# TamaDroppy.net
KiCad netlist of a schematic drawn in EAGLE
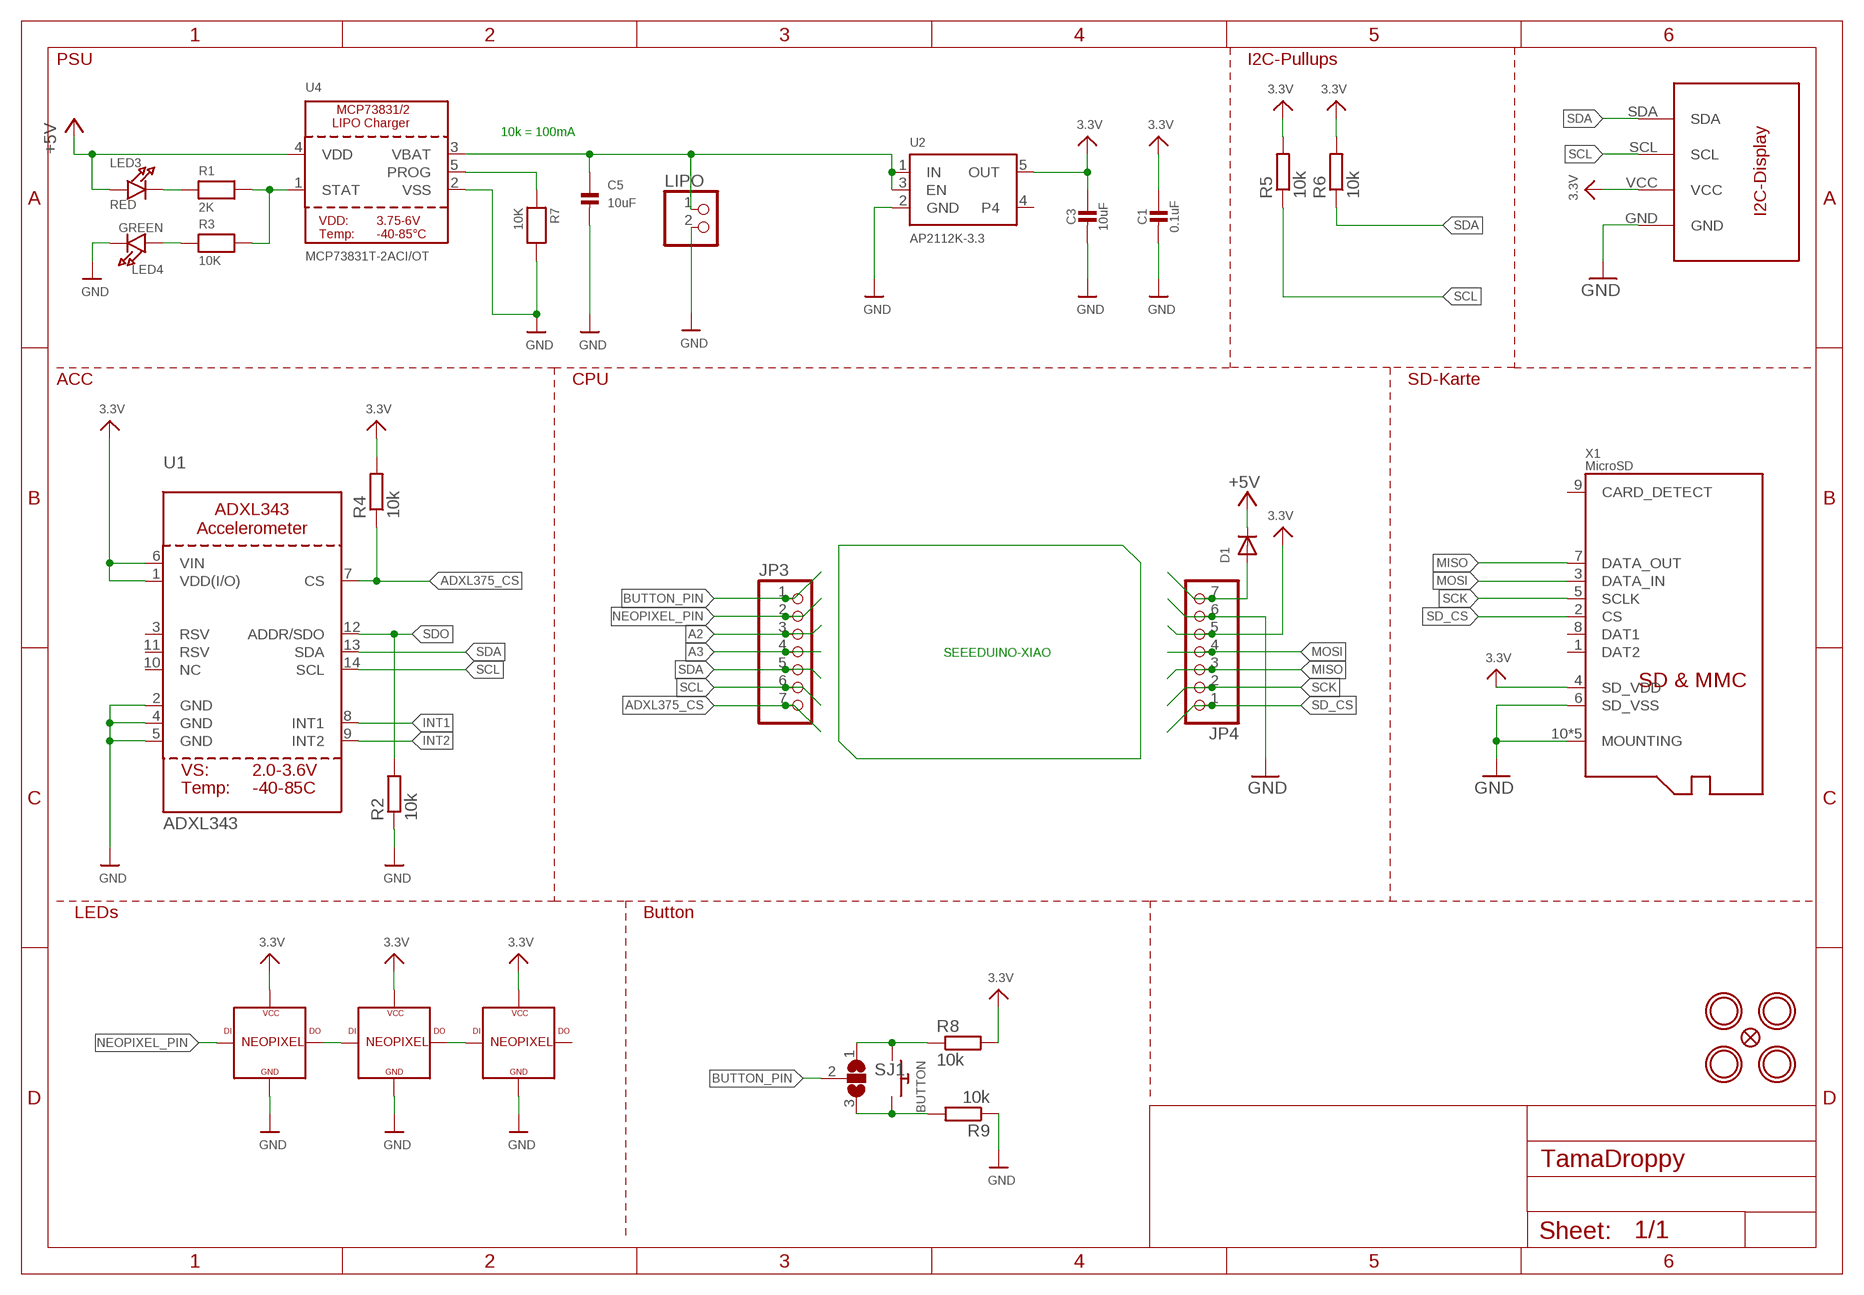
[diagram p0: schematic, sheet 1]

(export (version "E")
  (design (tool "Eeschema 10.0.6"))
  (components
    (comp (ref "BUTTON")
      (value "SWITCH_PUSHBUTTONC&K_KSS")
      (footprint "eagle-import:BTN_CK_KSS")
      (libsource (lib "eagle-import") (part "SWITCH_PUSHBUTTONC&K_KSS"))
    )
    (comp (ref "C1")
      (value "0.1uF")
      (footprint "eagle-import:0603-NO")
      (libsource (lib "eagle-import") (part "CAP_CERAMIC0603_NO"))
    )
    (comp (ref "C3")
      (value "10uF")
      (footprint "eagle-import:0805-NO")
      (libsource (lib "eagle-import") (part "CAP_CERAMIC0805-NOOUTLINE"))
    )
    (comp (ref "C5")
      (value "10uF")
      (footprint "eagle-import:0805-NO")
      (libsource (lib "eagle-import") (part "CAP_CERAMIC0805-NOOUTLINE"))
    )
    (comp (ref "D1")
      (value "DIODESOD-323F")
      (footprint "eagle-import:SOD-323F")
      (libsource (lib "eagle-import") (part "DIODESOD-323F"))
    )
    (comp (ref "FID3")
      (value "FIDUCIAL_1MM")
      (footprint "eagle-import:FIDUCIAL_1MM")
      (libsource (lib "eagle-import") (part "FIDUCIAL_1MM"))
    )
    (comp (ref "JP3")
      (value "HEADER-1X7THICKER")
      (footprint "eagle-import:1X07_ROUND_76")
      (libsource (lib "eagle-import") (part "HEADER-1X7THICKER"))
    )
    (comp (ref "JP4")
      (value "HEADER-1X7THICKER")
      (footprint "eagle-import:1X07_ROUND_76")
      (libsource (lib "eagle-import") (part "HEADER-1X7THICKER"))
    )
    (comp (ref "LED3")
      (value "RED")
      (footprint "eagle-import:CHIPLED_0603_NOOUTLINE")
      (libsource (lib "eagle-import") (part "LED0603_NOOUTLINE"))
    )
    (comp (ref "LED4")
      (value "GREEN")
      (footprint "eagle-import:CHIPLED_0603_NOOUTLINE")
      (libsource (lib "eagle-import") (part "LED0603_NOOUTLINE"))
    )
    (comp (ref "LIPO")
      (value "PINHD-1X2")
      (footprint "eagle-import:1X02")
      (libsource (lib "eagle-import") (part "PINHD-1X2"))
    )
    (comp (ref "R1")
      (value "2K")
      (footprint "eagle-import:0603-NO")
      (libsource (lib "eagle-import") (part "RESISTOR_0603_NOOUT"))
    )
    (comp (ref "R2")
      (value "10k")
      (footprint "eagle-import:M0805")
      (libsource (lib "eagle-import") (part "R-EU_M0805"))
    )
    (comp (ref "R3")
      (value "10K")
      (footprint "eagle-import:0603-NO")
      (libsource (lib "eagle-import") (part "RESISTOR_0603_NOOUT"))
    )
    (comp (ref "R4")
      (value "10k")
      (footprint "eagle-import:M0805")
      (libsource (lib "eagle-import") (part "R-EU_M0805"))
    )
    (comp (ref "R5")
      (value "10k")
      (footprint "eagle-import:M0805")
      (libsource (lib "eagle-import") (part "R-EU_M0805"))
    )
    (comp (ref "R6")
      (value "10k")
      (footprint "eagle-import:M0805")
      (libsource (lib "eagle-import") (part "R-EU_M0805"))
    )
    (comp (ref "R7")
      (value "10K")
      (footprint "eagle-import:0603-NO")
      (libsource (lib "eagle-import") (part "RESISTOR_0603_NOOUT"))
    )
    (comp (ref "R8")
      (value "10k")
      (footprint "eagle-import:M0805")
      (libsource (lib "eagle-import") (part "R-EU_M0805"))
    )
    (comp (ref "R9")
      (value "10k")
      (footprint "eagle-import:M0805")
      (libsource (lib "eagle-import") (part "R-EU_M0805"))
    )
    (comp (ref "SJ1")
      (value "SJ2W")
      (footprint "eagle-import:SJ_2")
      (libsource (lib "eagle-import") (part "SJ2W"))
    )
    (comp (ref "U$2")
      (value "MOUNTINGHOLE2.5")
      (footprint "eagle-import:MOUNTINGHOLE_2.5_PLATED")
      (libsource (lib "eagle-import") (part "MOUNTINGHOLE2.5"))
    )
    (comp (ref "U$16")
      (value "EASTRISING_0.66")
      (footprint "eagle-import:EASTRISING_0.66")
      (libsource (lib "eagle-import") (part "EASTRISING_0.66"))
    )
    (comp (ref "U$17")
      (value "MOUNTINGHOLE2.5")
      (footprint "eagle-import:MOUNTINGHOLE_2.5_PLATED")
      (libsource (lib "eagle-import") (part "MOUNTINGHOLE2.5"))
    )
    (comp (ref "U$19")
      (value "MOUNTINGHOLE2.5")
      (footprint "eagle-import:MOUNTINGHOLE_2.5_PLATED")
      (libsource (lib "eagle-import") (part "MOUNTINGHOLE2.5"))
    )
    (comp (ref "U$21")
      (value "MOUNTINGHOLE2.5")
      (footprint "eagle-import:MOUNTINGHOLE_2.5_PLATED")
      (libsource (lib "eagle-import") (part "MOUNTINGHOLE2.5"))
    )
    (comp (ref "U$31")
      (value "WS2812_BOB")
      (footprint "eagle-import:WS2812B")
      (libsource (lib "eagle-import") (part "WS2812_BOB"))
    )
    (comp (ref "U$32")
      (value "WS2812_BOB")
      (footprint "eagle-import:WS2812B")
      (libsource (lib "eagle-import") (part "WS2812_BOB"))
    )
    (comp (ref "U$33")
      (value "WS2812_BOB")
      (footprint "eagle-import:WS2812B")
      (libsource (lib "eagle-import") (part "WS2812_BOB"))
    )
    (comp (ref "U1")
      (value "ADXL343")
      (footprint "eagle-import:LGA14")
      (libsource (lib "eagle-import") (part "ACCEL_ADXL343"))
    )
    (comp (ref "U2")
      (value "AP2112K-3.3")
      (footprint "eagle-import:SOT23-5")
      (libsource (lib "eagle-import") (part "VREG_SOT23-5"))
    )
    (comp (ref "U4")
      (value "MCP73831T-2ACI/OT")
      (footprint "eagle-import:SOT23-5")
      (libsource (lib "eagle-import") (part "MCP73831/2"))
    )
    (comp (ref "X1")
      (value "MicroSD")
      (footprint "eagle-import:MOLEX_104031-0811")
      (libsource (lib "eagle-import") (part "MICROSD104031-0811"))
    )
  )
  (nets
    (net (code "1") (name "+5V") (class "Default")
      (node (ref "D1") (pin "C") (pinfunction "C_C") (pintype "passive"))
      (node (ref "LED3") (pin "A") (pinfunction "A_A") (pintype "passive"))
      (node (ref "U4") (pin "4") (pinfunction "VDD_4") (pintype "power_in"))
    )
    (net (code "2") (name "3.3V") (class "Default")
      (node (ref "C1") (pin "1") (pinfunction "1_1") (pintype "passive"))
      (node (ref "C3") (pin "1") (pinfunction "1_1") (pintype "passive"))
      (node (ref "JP4") (pin "5") (pinfunction "5_5") (pintype "passive"))
      (node (ref "R4") (pin "2") (pinfunction "2_2") (pintype "passive"))
      (node (ref "R5") (pin "2") (pinfunction "2_2") (pintype "passive"))
      (node (ref "R6") (pin "2") (pinfunction "2_2") (pintype "passive"))
      (node (ref "R8") (pin "2") (pinfunction "2_2") (pintype "passive"))
      (node (ref "U$16") (pin "VCC") (pinfunction "VCC_VCC") (pintype "bidirectional"))
      (node (ref "U$31") (pin "VCC1") (pinfunction "VCC_VCC1") (pintype "bidirectional"))
      (node (ref "U$31") (pin "VCC2") (pinfunction "VCC_VCC2") (pintype "bidirectional"))
      (node (ref "U$32") (pin "VCC1") (pinfunction "VCC_VCC1") (pintype "bidirectional"))
      (node (ref "U$32") (pin "VCC2") (pinfunction "VCC_VCC2") (pintype "bidirectional"))
      (node (ref "U$33") (pin "VCC1") (pinfunction "VCC_VCC1") (pintype "bidirectional"))
      (node (ref "U$33") (pin "VCC2") (pinfunction "VCC_VCC2") (pintype "bidirectional"))
      (node (ref "U1") (pin "1") (pinfunction "VDD(I/O)_1") (pintype "bidirectional"))
      (node (ref "U1") (pin "6") (pinfunction "VIN_6") (pintype "bidirectional"))
      (node (ref "U2") (pin "5") (pinfunction "OUT_5") (pintype "power_in"))
      (node (ref "X1") (pin "4") (pinfunction "SD_VDD_4") (pintype "power_in"))
    )
    (net (code "3") (name "A2") (class "Default")
      (node (ref "JP3") (pin "3") (pinfunction "3_3") (pintype "passive"))
    )
    (net (code "4") (name "A3") (class "Default")
      (node (ref "JP3") (pin "4") (pinfunction "4_4") (pintype "passive"))
    )
    (net (code "5") (name "ADXL375_CS") (class "Default")
      (node (ref "JP3") (pin "7") (pinfunction "7_7") (pintype "passive"))
      (node (ref "R4") (pin "1") (pinfunction "1_1") (pintype "passive"))
      (node (ref "U1") (pin "7") (pinfunction "CS_7") (pintype "bidirectional"))
    )
    (net (code "6") (name "BUTTON_PIN") (class "Default")
      (node (ref "JP3") (pin "1") (pinfunction "1_1") (pintype "passive"))
      (node (ref "SJ1") (pin "2") (pinfunction "2_2") (pintype "passive"))
    )
    (net (code "7") (name "GND") (class "Default")
      (node (ref "C1") (pin "2") (pinfunction "2_2") (pintype "passive"))
      (node (ref "C3") (pin "2") (pinfunction "2_2") (pintype "passive"))
      (node (ref "C5") (pin "2") (pinfunction "2_2") (pintype "passive"))
      (node (ref "JP4") (pin "6") (pinfunction "6_6") (pintype "passive"))
      (node (ref "LED4") (pin "C") (pinfunction "C_C") (pintype "passive"))
      (node (ref "LIPO") (pin "2") (pinfunction "2_2") (pintype "passive"))
      (node (ref "R2") (pin "1") (pinfunction "1_1") (pintype "passive"))
      (node (ref "R7") (pin "2") (pinfunction "2_2") (pintype "passive"))
      (node (ref "R9") (pin "1") (pinfunction "1_1") (pintype "passive"))
      (node (ref "U$16") (pin "GND") (pinfunction "GND_GND") (pintype "bidirectional"))
      (node (ref "U$31") (pin "GND1") (pinfunction "GND_GND1") (pintype "bidirectional"))
      (node (ref "U$31") (pin "GND2") (pinfunction "GND_GND2") (pintype "bidirectional"))
      (node (ref "U$32") (pin "GND1") (pinfunction "GND_GND1") (pintype "bidirectional"))
      (node (ref "U$32") (pin "GND2") (pinfunction "GND_GND2") (pintype "bidirectional"))
      (node (ref "U$33") (pin "GND1") (pinfunction "GND_GND1") (pintype "bidirectional"))
      (node (ref "U$33") (pin "GND2") (pinfunction "GND_GND2") (pintype "bidirectional"))
      (node (ref "U1") (pin "2") (pinfunction "GND_2") (pintype "bidirectional"))
      (node (ref "U1") (pin "4") (pinfunction "GND_4") (pintype "bidirectional"))
      (node (ref "U1") (pin "5") (pinfunction "GND_5") (pintype "bidirectional"))
      (node (ref "U2") (pin "2") (pinfunction "GND_2") (pintype "power_in"))
      (node (ref "U4") (pin "2") (pinfunction "VSS_2") (pintype "power_in"))
      (node (ref "X1") (pin "10") (pinfunction "MOUNTING_10") (pintype "passive"))
      (node (ref "X1") (pin "6") (pinfunction "SD_VSS_6") (pintype "power_in"))
      (node (ref "X1") (pin "G1") (pinfunction "MOUNTING_G1") (pintype "passive"))
      (node (ref "X1") (pin "G2") (pinfunction "MOUNTING_G2") (pintype "passive"))
      (node (ref "X1") (pin "G3") (pinfunction "MOUNTING_G3") (pintype "passive"))
      (node (ref "X1") (pin "G4") (pinfunction "MOUNTING_G4") (pintype "passive"))
    )
    (net (code "8") (name "INT1") (class "Default")
      (node (ref "U1") (pin "8") (pinfunction "INT1_8") (pintype "bidirectional"))
    )
    (net (code "9") (name "INT2") (class "Default")
      (node (ref "U1") (pin "9") (pinfunction "INT2_9") (pintype "bidirectional"))
    )
    (net (code "10") (name "MISO") (class "Default")
      (node (ref "JP4") (pin "3") (pinfunction "3_3") (pintype "passive"))
      (node (ref "X1") (pin "7") (pinfunction "DATA_OUT_7") (pintype "output"))
    )
    (net (code "11") (name "MOSI") (class "Default")
      (node (ref "JP4") (pin "4") (pinfunction "4_4") (pintype "passive"))
      (node (ref "X1") (pin "3") (pinfunction "DATA_IN_3") (pintype "input"))
    )
    (net (code "12") (name "NEOPIXEL_PIN") (class "Default")
      (node (ref "JP3") (pin "2") (pinfunction "2_2") (pintype "passive"))
      (node (ref "U$31") (pin "DIN") (pinfunction "DI_DIN") (pintype "bidirectional"))
    )
    (net (code "13") (name "Net-(BUTTON-PadP$1)") (class "Default")
      (node (ref "BUTTON") (pin "P$1") (pinfunction "P$1_P$1") (pintype "passive"))
      (node (ref "R8") (pin "1") (pinfunction "1_1") (pintype "passive"))
      (node (ref "SJ1") (pin "1") (pinfunction "1_1") (pintype "passive"))
    )
    (net (code "14") (name "Net-(BUTTON-PadP$2)") (class "Default")
      (node (ref "BUTTON") (pin "P$2") (pinfunction "P$2_P$2") (pintype "passive"))
      (node (ref "R9") (pin "2") (pinfunction "2_2") (pintype "passive"))
      (node (ref "SJ1") (pin "3") (pinfunction "3_3") (pintype "passive"))
    )
    (net (code "15") (name "Net-(D1-PadA)") (class "Default")
      (node (ref "D1") (pin "A") (pinfunction "A_A") (pintype "passive"))
      (node (ref "JP4") (pin "7") (pinfunction "7_7") (pintype "passive"))
    )
    (net (code "16") (name "Net-(LED3-PadC)") (class "Default")
      (node (ref "LED3") (pin "C") (pinfunction "C_C") (pintype "passive"))
      (node (ref "R1") (pin "1") (pinfunction "1_1") (pintype "passive"))
    )
    (net (code "17") (name "Net-(LED4-PadA)") (class "Default")
      (node (ref "LED4") (pin "A") (pinfunction "A_A") (pintype "passive"))
      (node (ref "R3") (pin "1") (pinfunction "1_1") (pintype "passive"))
    )
    (net (code "18") (name "Net-(U$31-DO)") (class "Default")
      (node (ref "U$31") (pin "DOUT") (pinfunction "DO_DOUT") (pintype "bidirectional"))
      (node (ref "U$32") (pin "DIN") (pinfunction "DI_DIN") (pintype "bidirectional"))
    )
    (net (code "19") (name "Net-(U$32-DO)") (class "Default")
      (node (ref "U$32") (pin "DOUT") (pinfunction "DO_DOUT") (pintype "bidirectional"))
      (node (ref "U$33") (pin "DIN") (pinfunction "DI_DIN") (pintype "bidirectional"))
    )
    (net (code "20") (name "Net-(U2-EN)") (class "Default")
      (node (ref "C5") (pin "1") (pinfunction "1_1") (pintype "passive"))
      (node (ref "LIPO") (pin "1") (pinfunction "1_1") (pintype "passive"))
      (node (ref "U2") (pin "1") (pinfunction "IN_1") (pintype "power_in"))
      (node (ref "U2") (pin "3") (pinfunction "EN_3") (pintype "input"))
      (node (ref "U4") (pin "3") (pinfunction "VBAT_3") (pintype "power_in"))
    )
    (net (code "21") (name "Net-(U4-PROG)") (class "Default")
      (node (ref "R7") (pin "1") (pinfunction "1_1") (pintype "passive"))
      (node (ref "U4") (pin "5") (pinfunction "PROG_5") (pintype "input"))
    )
    (net (code "22") (name "Net-(U4-STAT)") (class "Default")
      (node (ref "R1") (pin "2") (pinfunction "2_2") (pintype "passive"))
      (node (ref "R3") (pin "2") (pinfunction "2_2") (pintype "passive"))
      (node (ref "U4") (pin "1") (pinfunction "STAT_1") (pintype "output"))
    )
    (net (code "23") (name "SCK") (class "Default")
      (node (ref "JP4") (pin "2") (pinfunction "2_2") (pintype "passive"))
      (node (ref "X1") (pin "5") (pinfunction "SCLK_5") (pintype "input"))
    )
    (net (code "24") (name "SCL") (class "Default")
      (node (ref "JP3") (pin "6") (pinfunction "6_6") (pintype "passive"))
      (node (ref "R5") (pin "1") (pinfunction "1_1") (pintype "passive"))
      (node (ref "U$16") (pin "SCL") (pinfunction "SCL_SCL") (pintype "bidirectional"))
      (node (ref "U1") (pin "14") (pinfunction "SCL_14") (pintype "bidirectional"))
    )
    (net (code "25") (name "SDA") (class "Default")
      (node (ref "JP3") (pin "5") (pinfunction "5_5") (pintype "passive"))
      (node (ref "R6") (pin "1") (pinfunction "1_1") (pintype "passive"))
      (node (ref "U$16") (pin "SDA") (pinfunction "SDA_SDA") (pintype "bidirectional"))
      (node (ref "U1") (pin "13") (pinfunction "SDA_13") (pintype "bidirectional"))
    )
    (net (code "26") (name "SDO") (class "Default")
      (node (ref "R2") (pin "2") (pinfunction "2_2") (pintype "passive"))
      (node (ref "U1") (pin "12") (pinfunction "ADDR/SDO_12") (pintype "bidirectional"))
    )
    (net (code "27") (name "SD_CS") (class "Default")
      (node (ref "JP4") (pin "1") (pinfunction "1_1") (pintype "passive"))
      (node (ref "X1") (pin "2") (pinfunction "CS_2") (pintype "input"))
    )
    (net (code "28") (name "unconnected-(U$33-DO-PadDOUT)") (class "Default")
      (node (ref "U$33") (pin "DOUT") (pinfunction "DO_DOUT") (pintype "bidirectional"))
    )
    (net (code "29") (name "unconnected-(U1-NC-Pad10)") (class "Default")
      (node (ref "U1") (pin "10") (pinfunction "NC_10") (pintype "bidirectional"))
    )
    (net (code "30") (name "unconnected-(U1-RSV-Pad3)") (class "Default")
      (node (ref "U1") (pin "3") (pinfunction "RSV_3") (pintype "bidirectional"))
    )
    (net (code "31") (name "unconnected-(U1-RSV-Pad11)") (class "Default")
      (node (ref "U1") (pin "11") (pinfunction "RSV_11") (pintype "bidirectional"))
    )
    (net (code "32") (name "unconnected-(U2-P4-Pad4)") (class "Default")
      (node (ref "U2") (pin "4") (pinfunction "P4_4") (pintype "bidirectional"))
    )
    (net (code "33") (name "unconnected-(X1-CARD_DETECT-Pad9)") (class "Default")
      (node (ref "X1") (pin "9") (pinfunction "CARD_DETECT_9") (pintype "passive"))
    )
    (net (code "34") (name "unconnected-(X1-DAT1-Pad8)") (class "Default")
      (node (ref "X1") (pin "8") (pinfunction "DAT1_8") (pintype "bidirectional"))
    )
    (net (code "35") (name "unconnected-(X1-DAT2-Pad1)") (class "Default")
      (node (ref "X1") (pin "1") (pinfunction "DAT2_1") (pintype "bidirectional"))
    )
  )
)
